# Lab10.net
KiCad netlist of a schematic drawn in EAGLE
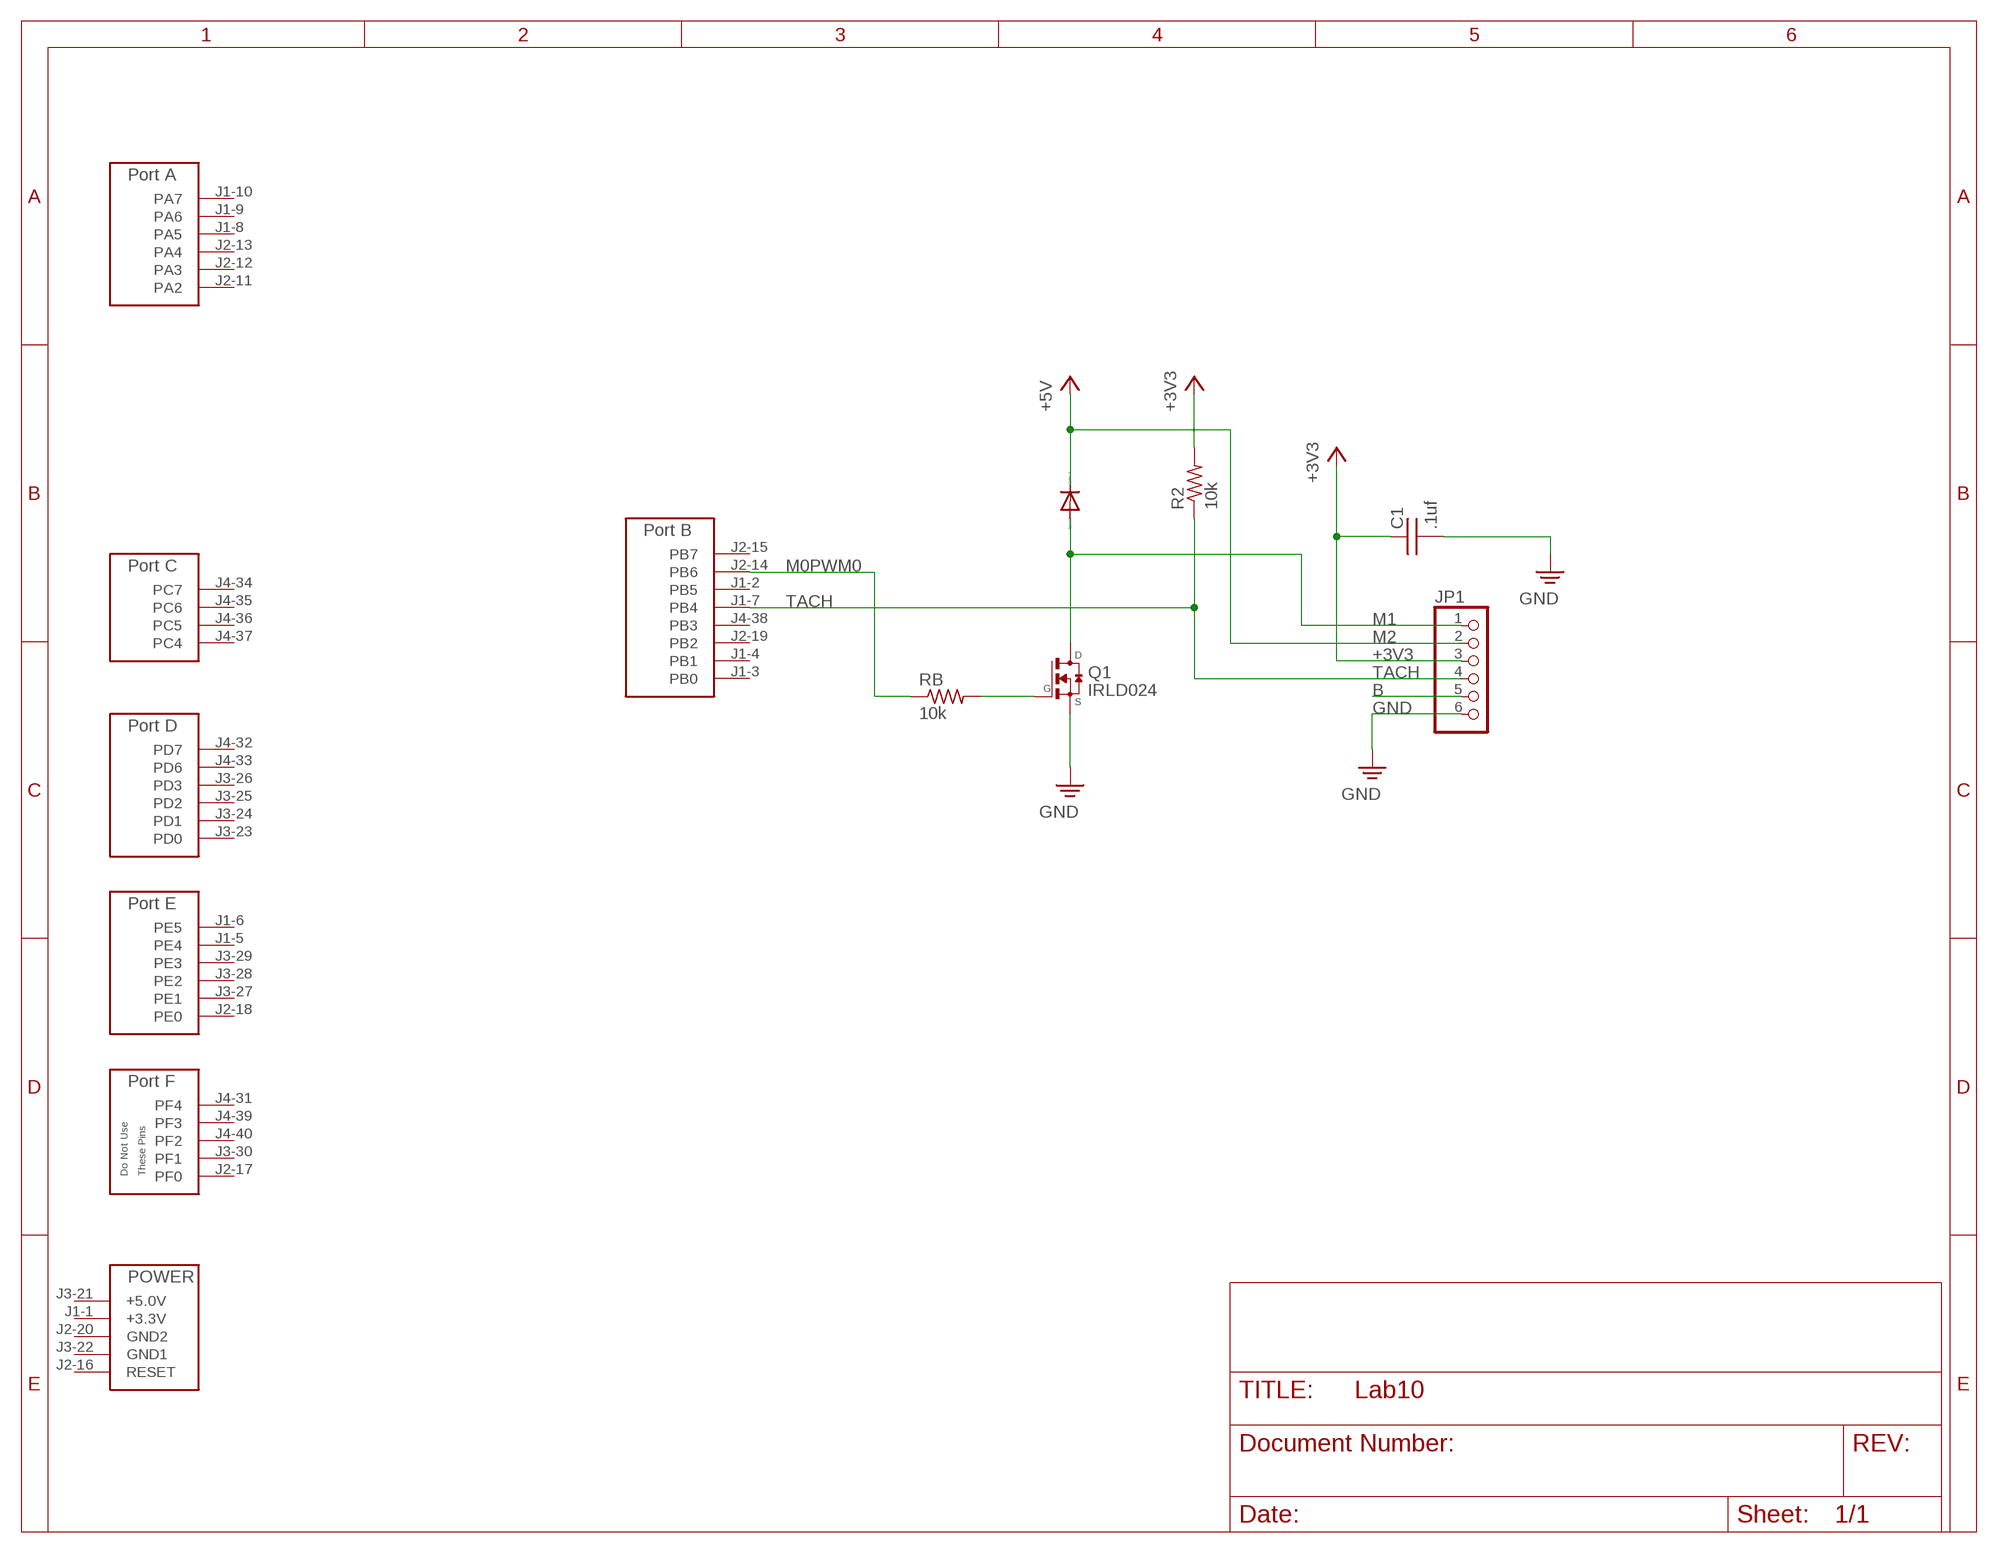
[diagram p0: schematic, sheet 1]

(export (version "E")
  (design (tool "Eeschema 10.0.6"))
  (components
    (comp (ref "C1")
      (value ".1uf")
      (footprint "eagle-import:CAP100MIL")
      (libsource (lib "eagle-import") (part "CAPACITOR025-024X044"))
    )
    (comp (ref "D1")
      (value "1N914DO35-7")
      (footprint "eagle-import:DO35-7")
      (libsource (lib "eagle-import") (part "1N914DO35-7"))
    )
    (comp (ref "JP1")
      (value "PINHD-1X6")
      (footprint "eagle-import:1X06")
      (libsource (lib "eagle-import") (part "PINHD-1X6"))
    )
    (comp (ref "Q1")
      (value "IRLD024")
      (footprint "eagle-import:IRLD024")
      (libsource (lib "eagle-import") (part "IRLD024"))
    )
    (comp (ref "R2")
      (value "10k")
      (footprint "eagle-import:RES200MIL")
      (libsource (lib "eagle-import") (part "RESISTOR0204/5"))
    )
    (comp (ref "RB")
      (value "10k")
      (footprint "eagle-import:RES200MIL")
      (libsource (lib "eagle-import") (part "RESISTOR0204/5"))
    )
    (comp (ref "U$1")
      (value "TM4C_BP")
      (footprint "eagle-import:TM4C_BOOSTER_PACK")
      (libsource (lib "eagle-import") (part "TM4C_BP"))
    )
  )
  (nets
    (net (code "1") (name "+3V3") (class "Default")
      (node (ref "C1") (pin "1") (pinfunction "1_1") (pintype "passive"))
      (node (ref "JP1") (pin "3") (pinfunction "3_3") (pintype "passive"))
      (node (ref "R2") (pin "2") (pinfunction "2_2") (pintype "passive"))
    )
    (net (code "2") (name "+5V") (class "Default")
      (node (ref "D1") (pin "C") (pinfunction "C_C") (pintype "passive"))
      (node (ref "JP1") (pin "2") (pinfunction "2_2") (pintype "passive"))
    )
    (net (code "3") (name "/B") (class "Default")
      (node (ref "JP1") (pin "5") (pinfunction "5_5") (pintype "passive"))
    )
    (net (code "4") (name "/M0PWM0") (class "Default")
      (node (ref "RB") (pin "1") (pinfunction "1_1") (pintype "passive"))
      (node (ref "U$1") (pin "J2-14") (pinfunction "PB6_J2-14") (pintype "bidirectional"))
    )
    (net (code "5") (name "/M1") (class "Default")
      (node (ref "D1") (pin "A") (pinfunction "A_A") (pintype "passive"))
      (node (ref "JP1") (pin "1") (pinfunction "1_1") (pintype "passive"))
      (node (ref "Q1") (pin "P$1") (pinfunction "D_P$1") (pintype "passive"))
    )
    (net (code "6") (name "/TACH") (class "Default")
      (node (ref "JP1") (pin "4") (pinfunction "4_4") (pintype "passive"))
      (node (ref "R2") (pin "1") (pinfunction "1_1") (pintype "passive"))
      (node (ref "U$1") (pin "J1-7") (pinfunction "PB4_J1-7") (pintype "bidirectional"))
    )
    (net (code "7") (name "GND") (class "Default")
      (node (ref "C1") (pin "2") (pinfunction "2_2") (pintype "passive"))
      (node (ref "JP1") (pin "6") (pinfunction "6_6") (pintype "passive"))
      (node (ref "Q1") (pin "P$4") (pinfunction "S_P$4") (pintype "passive"))
    )
    (net (code "8") (name "Net-(Q1-G)") (class "Default")
      (node (ref "Q1") (pin "P$3") (pinfunction "G_P$3") (pintype "passive"))
      (node (ref "RB") (pin "2") (pinfunction "2_2") (pintype "passive"))
    )
    (net (code "9") (name "unconnected-(U$1A-PA2-PadJ2-11)") (class "Default")
      (node (ref "U$1") (pin "J2-11") (pinfunction "PA2_J2-11") (pintype "bidirectional"))
    )
    (net (code "10") (name "unconnected-(U$1A-PA3-PadJ2-12)") (class "Default")
      (node (ref "U$1") (pin "J2-12") (pinfunction "PA3_J2-12") (pintype "bidirectional"))
    )
    (net (code "11") (name "unconnected-(U$1A-PA4-PadJ2-13)") (class "Default")
      (node (ref "U$1") (pin "J2-13") (pinfunction "PA4_J2-13") (pintype "bidirectional"))
    )
    (net (code "12") (name "unconnected-(U$1A-PA5-PadJ1-8)") (class "Default")
      (node (ref "U$1") (pin "J1-8") (pinfunction "PA5_J1-8") (pintype "bidirectional"))
    )
    (net (code "13") (name "unconnected-(U$1A-PA6-PadJ1-9)") (class "Default")
      (node (ref "U$1") (pin "J1-9") (pinfunction "PA6_J1-9") (pintype "bidirectional"))
    )
    (net (code "14") (name "unconnected-(U$1A-PA7-PadJ1-10)") (class "Default")
      (node (ref "U$1") (pin "J1-10") (pinfunction "PA7_J1-10") (pintype "bidirectional"))
    )
    (net (code "15") (name "unconnected-(U$1B-PB0-PadJ1-3)") (class "Default")
      (node (ref "U$1") (pin "J1-3") (pinfunction "PB0_J1-3") (pintype "bidirectional"))
    )
    (net (code "16") (name "unconnected-(U$1B-PB1-PadJ1-4)") (class "Default")
      (node (ref "U$1") (pin "J1-4") (pinfunction "PB1_J1-4") (pintype "bidirectional"))
    )
    (net (code "17") (name "unconnected-(U$1B-PB2-PadJ2-19)") (class "Default")
      (node (ref "U$1") (pin "J2-19") (pinfunction "PB2_J2-19") (pintype "bidirectional"))
    )
    (net (code "18") (name "unconnected-(U$1B-PB3-PadJ4-38)") (class "Default")
      (node (ref "U$1") (pin "J4-38") (pinfunction "PB3_J4-38") (pintype "bidirectional"))
    )
    (net (code "19") (name "unconnected-(U$1B-PB5-PadJ1-2)") (class "Default")
      (node (ref "U$1") (pin "J1-2") (pinfunction "PB5_J1-2") (pintype "bidirectional"))
    )
    (net (code "20") (name "unconnected-(U$1B-PB7-PadJ2-15)") (class "Default")
      (node (ref "U$1") (pin "J2-15") (pinfunction "PB7_J2-15") (pintype "bidirectional"))
    )
    (net (code "21") (name "unconnected-(U$1C-PC4-PadJ4-37)") (class "Default")
      (node (ref "U$1") (pin "J4-37") (pinfunction "PC4_J4-37") (pintype "bidirectional"))
    )
    (net (code "22") (name "unconnected-(U$1C-PC5-PadJ4-36)") (class "Default")
      (node (ref "U$1") (pin "J4-36") (pinfunction "PC5_J4-36") (pintype "bidirectional"))
    )
    (net (code "23") (name "unconnected-(U$1C-PC6-PadJ4-35)") (class "Default")
      (node (ref "U$1") (pin "J4-35") (pinfunction "PC6_J4-35") (pintype "bidirectional"))
    )
    (net (code "24") (name "unconnected-(U$1C-PC7-PadJ4-34)") (class "Default")
      (node (ref "U$1") (pin "J4-34") (pinfunction "PC7_J4-34") (pintype "bidirectional"))
    )
    (net (code "25") (name "unconnected-(U$1D-PD0-PadJ3-23)") (class "Default")
      (node (ref "U$1") (pin "J3-23") (pinfunction "PD0_J3-23") (pintype "bidirectional"))
    )
    (net (code "26") (name "unconnected-(U$1D-PD1-PadJ3-24)") (class "Default")
      (node (ref "U$1") (pin "J3-24") (pinfunction "PD1_J3-24") (pintype "bidirectional"))
    )
    (net (code "27") (name "unconnected-(U$1D-PD2-PadJ3-25)") (class "Default")
      (node (ref "U$1") (pin "J3-25") (pinfunction "PD2_J3-25") (pintype "bidirectional"))
    )
    (net (code "28") (name "unconnected-(U$1D-PD3-PadJ3-26)") (class "Default")
      (node (ref "U$1") (pin "J3-26") (pinfunction "PD3_J3-26") (pintype "bidirectional"))
    )
    (net (code "29") (name "unconnected-(U$1D-PD6-PadJ4-33)") (class "Default")
      (node (ref "U$1") (pin "J4-33") (pinfunction "PD6_J4-33") (pintype "bidirectional"))
    )
    (net (code "30") (name "unconnected-(U$1D-PD7-PadJ4-32)") (class "Default")
      (node (ref "U$1") (pin "J4-32") (pinfunction "PD7_J4-32") (pintype "bidirectional"))
    )
    (net (code "31") (name "unconnected-(U$1E-PE0-PadJ2-18)") (class "Default")
      (node (ref "U$1") (pin "J2-18") (pinfunction "PE0_J2-18") (pintype "bidirectional"))
    )
    (net (code "32") (name "unconnected-(U$1E-PE1-PadJ3-27)") (class "Default")
      (node (ref "U$1") (pin "J3-27") (pinfunction "PE1_J3-27") (pintype "bidirectional"))
    )
    (net (code "33") (name "unconnected-(U$1E-PE2-PadJ3-28)") (class "Default")
      (node (ref "U$1") (pin "J3-28") (pinfunction "PE2_J3-28") (pintype "bidirectional"))
    )
    (net (code "34") (name "unconnected-(U$1E-PE3-PadJ3-29)") (class "Default")
      (node (ref "U$1") (pin "J3-29") (pinfunction "PE3_J3-29") (pintype "bidirectional"))
    )
    (net (code "35") (name "unconnected-(U$1E-PE4-PadJ1-5)") (class "Default")
      (node (ref "U$1") (pin "J1-5") (pinfunction "PE4_J1-5") (pintype "bidirectional"))
    )
    (net (code "36") (name "unconnected-(U$1E-PE5-PadJ1-6)") (class "Default")
      (node (ref "U$1") (pin "J1-6") (pinfunction "PE5_J1-6") (pintype "bidirectional"))
    )
    (net (code "37") (name "unconnected-(U$1F-PF0-PadJ2-17)") (class "Default")
      (node (ref "U$1") (pin "J2-17") (pinfunction "PF0_J2-17") (pintype "bidirectional"))
    )
    (net (code "38") (name "unconnected-(U$1F-PF1-PadJ3-30)") (class "Default")
      (node (ref "U$1") (pin "J3-30") (pinfunction "PF1_J3-30") (pintype "bidirectional"))
    )
    (net (code "39") (name "unconnected-(U$1F-PF2-PadJ4-40)") (class "Default")
      (node (ref "U$1") (pin "J4-40") (pinfunction "PF2_J4-40") (pintype "bidirectional"))
    )
    (net (code "40") (name "unconnected-(U$1F-PF3-PadJ4-39)") (class "Default")
      (node (ref "U$1") (pin "J4-39") (pinfunction "PF3_J4-39") (pintype "bidirectional"))
    )
    (net (code "41") (name "unconnected-(U$1F-PF4-PadJ4-31)") (class "Default")
      (node (ref "U$1") (pin "J4-31") (pinfunction "PF4_J4-31") (pintype "bidirectional"))
    )
    (net (code "42") (name "unconnected-(U$1G-+3.3V-PadJ1-1)") (class "Default")
      (node (ref "U$1") (pin "J1-1") (pinfunction "+3.3V_J1-1") (pintype "bidirectional"))
    )
    (net (code "43") (name "unconnected-(U$1G-+5.0V-PadJ3-21)") (class "Default")
      (node (ref "U$1") (pin "J3-21") (pinfunction "+5.0V_J3-21") (pintype "bidirectional"))
    )
    (net (code "44") (name "unconnected-(U$1G-GND1-PadJ3-22)") (class "Default")
      (node (ref "U$1") (pin "J3-22") (pinfunction "GND1_J3-22") (pintype "bidirectional"))
    )
    (net (code "45") (name "unconnected-(U$1G-GND2-PadJ2-20)") (class "Default")
      (node (ref "U$1") (pin "J2-20") (pinfunction "GND2_J2-20") (pintype "bidirectional"))
    )
    (net (code "46") (name "unconnected-(U$1G-RESET-PadJ2-16)") (class "Default")
      (node (ref "U$1") (pin "J2-16") (pinfunction "RESET_J2-16") (pintype "bidirectional"))
    )
  )
)
